# Sheet1.net
KiCad netlist of a schematic drawn in Altium Designer
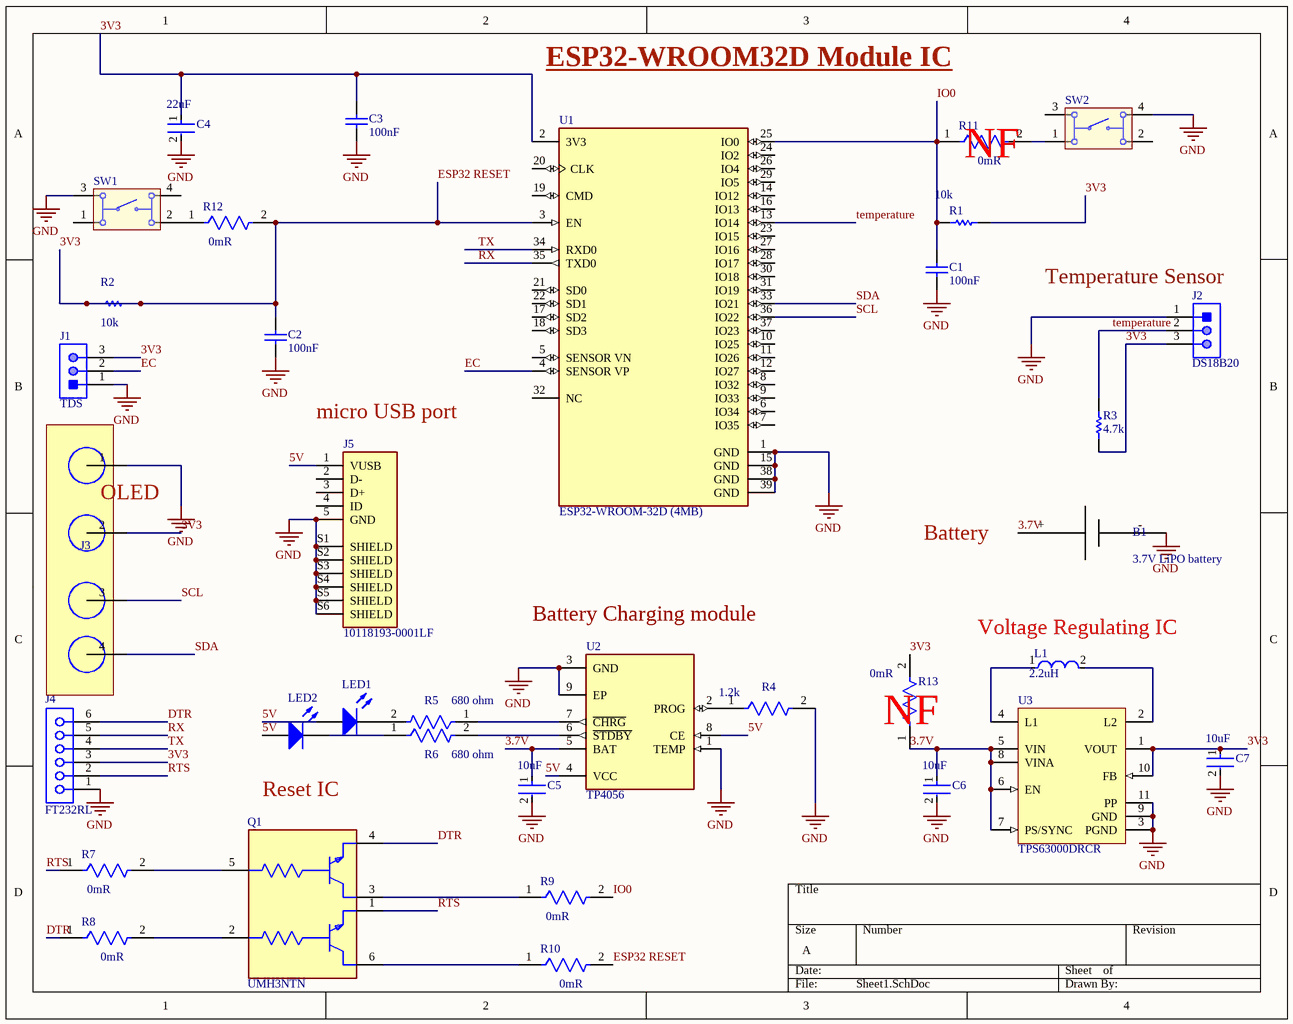
[diagram p0: Sheet1.SchDoc]

(export (version "E")
  (design (tool "Eeschema 10.0.6"))
  (components
    (comp (ref "B1")
      (value "3.7V LiPO battery")
      (footprint "Battery_lipo")
      (libsource (lib "*") (part "Battery"))
    )
    (comp (ref "C1")
      (value "MD015E104MAB")
      (footprint "AVX-MD01")
      (description "Ceramic Capacitor, 0.1 uF, +/- 20%, 50 V, -55 to 125 degC, 2-Pin THD (MD01), Bulk")
      (fields (field (name "MANUFACTURER") "AVX") (field (name "CAPACITANCE") "100nF"))
      (libsource (lib "Altium Content Vault") (part "CAP-NP-2"))
    )
    (comp (ref "C2")
      (value "MD015E104MAB")
      (footprint "AVX-MD01")
      (description "Ceramic Capacitor, 0.1 uF, +/- 20%, 50 V, -55 to 125 degC, 2-Pin THD (MD01), Bulk")
      (fields (field (name "MANUFACTURER") "AVX") (field (name "CAPACITANCE") "100nF"))
      (libsource (lib "Altium Content Vault") (part "CAP-NP-2"))
    )
    (comp (ref "C3")
      (value "MD015E104MAB")
      (footprint "AVX-MD01")
      (description "Ceramic Capacitor, 0.1 uF, +/- 20%, 50 V, -55 to 125 degC, 2-Pin THD (MD01), Bulk")
      (fields (field (name "MANUFACTURER") "AVX") (field (name "CAPACITANCE") "100nF"))
      (libsource (lib "Altium Content Vault") (part "CAP-NP-2"))
    )
    (comp (ref "C4")
      (value "RCER71E226MWM1H03A")
      (footprint "FP-RCEWM1-MFG")
      (description "CAP CER 22UF 25V X7R RADIAL")
      (fields (field (name "CAPACITANCE") "22uF") (field (name "TOLERANCE") "20%"))
      (libsource (lib "Altium Content Vault") (part "02cd4be3c70576c341d710602a673aa"))
    )
    (comp (ref "C5")
      (value "RCER71H106MWK1H03B")
      (footprint "FP-RCEWM1-MFG")
      (description "Cap Ceramic 10uF 50V X7R ±20% Radial 5mm +125°C Automotive Ammo Pack")
      (fields
        (field (name "CAPACITANCE") "10uF")
        (field (name "TOLERANCE") "20%")
        (field (name "VOLTAGE") "50V")
      )
      (libsource (lib "Altium Content Vault") (part "02cd4be3c70576c341d710602a673aa"))
    )
    (comp (ref "C6")
      (value "ECEA1VKN100")
      (footprint "FP-RAD-TH-D_6_3_0_5-L_7_1-MFG")
      (description "Aluminum Electrolytic Capacitors (Radial Lead Type) 10uF ±20% 35V")
      (fields (field (name "TOLERANCE") "20%") (field (name "CAPACITANCE") "10uF"))
      (libsource (lib "Altium Content Vault") (part "b4654b650e69147ec39a6b967a45e02"))
    )
    (comp (ref "C7")
      (value "ECEA1VKN100")
      (footprint "FP-RAD-TH-D_6_3_0_5-L_7_1-MFG")
      (description "Aluminum Electrolytic Capacitors (Radial Lead Type) 10uF ±20% 35V")
      (fields (field (name "TOLERANCE") "20%") (field (name "CAPACITANCE") "10uF"))
      (libsource (lib "Altium Content Vault") (part "b4654b650e69147ec39a6b967a45e02"))
    )
    (comp (ref "J1")
      (value "TDS")
      (footprint "MOLX-22-23-2031_V")
      (description "Male Header, Pitch 2.54 mm, 1 x 3 Position, Height 8.18 mm, Tail Length 3.56 mm, RoHS, Bulk")
      (fields (field (name "MANUFACTURER") "Molex"))
      (libsource (lib "Altium Content Vault") (part "CN-1P-M-R3"))
    )
    (comp (ref "J2")
      (value "DS18B20")
      (footprint "MOLX-22-23-2031_V")
      (description "Male Header, Pitch 2.54 mm, 1 x 3 Position, Height 8.18 mm, Tail Length 3.56 mm, RoHS, Bulk")
      (fields (field (name "MANUFACTURER") "Molex"))
      (libsource (lib "") (part "CN-1P-M-R3_1"))
    )
    (comp (ref "J3")
      (value "OLED")
      (footprint "female header")
      (libsource (lib "*") (part "4 PIN FEMALE HEADER"))
    )
    (comp (ref "J4")
      (value "FT232RL")
      (footprint "SMTC-SSW-106-02-X-S-RA")
      (fields (field (name "PARTNUMBER") "SSW-106-02-G-S-RA") (field (name "MANUFACTURER") "Samtec"))
      (libsource (lib "Altium Content Vault") (part "SMTC-SSW-106-02-X-S-X"))
    )
    (comp (ref "J5")
      (value "10118193-0001LF")
      (footprint "AMPHENOL_10118193-0001LF")
      (libsource (lib "Schlib1") (part "10118193-0001LF"))
    )
    (comp (ref "L1")
      (value "LQM2HPN2R2MJ0L")
      (footprint "FP-LQM2HPN_J0-IPC_A")
      (description "Multilayer Type Inductor for Power Lines, 1008 (2520), 2.2μH, 20%, 0.15Ω, 1000mA")
      (fields (field (name "TOLERANCE") "20%") (field (name "INDUCTANCE") "2.2uH"))
      (libsource (lib "Altium Content Vault") (part "725321dda6339637d4d059423bc1c3c"))
    )
    (comp (ref "LED1")
      (value "151051BS04000")
      (footprint "Type 5mm")
      (description "THT LED round mono-color color lens, WL-TMRW, Blue")
      (fields (field (name "MANUFACTURER") "Wuerth Elektronik"))
      (libsource (lib "Altium Content Vault") (part "WE-LED_K1A2-2"))
    )
    (comp (ref "LED2")
      (value "151051BS04000")
      (footprint "Type 5mm")
      (description "THT LED round mono-color color lens, WL-TMRW, Blue")
      (fields (field (name "MANUFACTURER") "Wuerth Elektronik"))
      (libsource (lib "Altium Content Vault") (part "WE-LED_K1A2-2"))
    )
    (comp (ref "Q1")
      (value "UMH3NTN")
      (footprint "FP-UMT6-IPC_C")
      (description "TRANS 2NPN PREBIAS 0.15W UMT6")
      (libsource (lib "Altium Content Vault") (part "8b681bbdef8deb96797ed10fcd55d9e"))
    )
    (comp (ref "R1")
      (value "OD103JE")
      (footprint "OMTE-RES7X2.5-2")
      (fields
        (field (name "RESISTANCE (OHMS)") "10k")
        (field (name "TOLERANCE") "±5%")
        (field (name "MANUFACTURER") "Ohmite")
      )
      (libsource (lib "Altium Content Vault") (part "RES-2"))
    )
    (comp (ref "R2")
      (value "OD103JE")
      (footprint "OMTE-RES7X2.5-2")
      (fields
        (field (name "RESISTANCE (OHMS)") "10k")
        (field (name "TOLERANCE") "±5%")
        (field (name "MANUFACTURER") "Ohmite")
      )
      (libsource (lib "Altium Content Vault") (part "RES-2"))
    )
    (comp (ref "R3")
      (value "OD103JE")
      (footprint "OMTE-RES7X2.5-2")
      (fields
        (field (name "RESISTANCE (OHMS)") "4.7k")
        (field (name "TOLERANCE") "±5%")
        (field (name "MANUFACTURER") "Ohmite")
      )
      (libsource (lib "Altium Content Vault") (part "RES-2"))
    )
    (comp (ref "R4")
      (value "MRS25000C9530FCT00")
      (footprint "FP-MRS25-MFG")
      (description "RES 953 OHM 0.6W 1% AXIAL")
      (fields (field (name "RESISTANCE") "1.2k") (field (name "TOLERANCE") "1%"))
      (libsource (lib "Altium Content Vault") (part "1029c3af85768c4190bb7ad29bc67b5"))
    )
    (comp (ref "R5")
      (value "MRS25000C9530FCT00")
      (footprint "FP-MRS25-MFG")
      (description "RES 953 OHM 0.6W 1% AXIAL")
      (fields (field (name "RESISTANCE") "680 ohm") (field (name "TOLERANCE") "1%"))
      (libsource (lib "Altium Content Vault") (part "1029c3af85768c4190bb7ad29bc67b5"))
    )
    (comp (ref "R6")
      (value "MRS25000C9530FCT00")
      (footprint "FP-MRS25-MFG")
      (description "RES 953 OHM 0.6W 1% AXIAL")
      (fields (field (name "RESISTANCE") "680 ohm") (field (name "TOLERANCE") "1%"))
      (libsource (lib "Altium Content Vault") (part "1029c3af85768c4190bb7ad29bc67b5"))
    )
    (comp (ref "R7")
      (value "ZOR-25-R-52-0R")
      (footprint "FP-ZOR-25-R-52-0R-MFG")
      (description "RES 0 OHM JUMPER 1/4W AXIAL")
      (fields (field (name "TOLERANCE") "5%") (field (name "RESISTANCE") "0mR"))
      (libsource (lib "Altium Content Vault") (part "d029466b076adaef5daba0b7f088f1c"))
    )
    (comp (ref "R8")
      (value "ZOR-25-R-52-0R")
      (footprint "FP-ZOR-25-R-52-0R-MFG")
      (description "RES 0 OHM JUMPER 1/4W AXIAL")
      (fields (field (name "TOLERANCE") "5%") (field (name "RESISTANCE") "0mR"))
      (libsource (lib "Altium Content Vault") (part "d029466b076adaef5daba0b7f088f1c"))
    )
    (comp (ref "R9")
      (value "ZOR-25-R-52-0R")
      (footprint "FP-ZOR-25-R-52-0R-MFG")
      (description "RES 0 OHM JUMPER 1/4W AXIAL")
      (fields (field (name "TOLERANCE") "5%") (field (name "RESISTANCE") "0mR"))
      (libsource (lib "Altium Content Vault") (part "d029466b076adaef5daba0b7f088f1c"))
    )
    (comp (ref "R10")
      (value "ZOR-25-R-52-0R")
      (footprint "FP-ZOR-25-R-52-0R-MFG")
      (description "RES 0 OHM JUMPER 1/4W AXIAL")
      (fields (field (name "TOLERANCE") "5%") (field (name "RESISTANCE") "0mR"))
      (libsource (lib "Altium Content Vault") (part "d029466b076adaef5daba0b7f088f1c"))
    )
    (comp (ref "R11")
      (value "ZOR-25-R-52-0R")
      (footprint "FP-ZOR-25-R-52-0R-MFG")
      (description "RES 0 OHM JUMPER 1/4W AXIAL")
      (fields (field (name "TOLERANCE") "5%") (field (name "RESISTANCE") "0mR"))
      (libsource (lib "Altium Content Vault") (part "d029466b076adaef5daba0b7f088f1c"))
    )
    (comp (ref "R12")
      (value "ZOR-25-R-52-0R")
      (footprint "FP-ZOR-25-R-52-0R-MFG")
      (description "RES 0 OHM JUMPER 1/4W AXIAL")
      (fields (field (name "TOLERANCE") "5%") (field (name "RESISTANCE") "0mR"))
      (libsource (lib "Altium Content Vault") (part "d029466b076adaef5daba0b7f088f1c"))
    )
    (comp (ref "R13")
      (value "ZOR-25-R-52-0R")
      (footprint "FP-ZOR-25-R-52-0R-MFG")
      (description "RES 0 OHM JUMPER 1/4W AXIAL")
      (fields (field (name "TOLERANCE") "5%") (field (name "RESISTANCE") "0mR"))
      (libsource (lib "Altium Content Vault") (part "d029466b076adaef5daba0b7f088f1c"))
    )
    (comp (ref "SW1")
      (value "430156050726")
      (footprint "430156050726")
      (description "WS-TATV THT Tact Switch 6X6 mm")
      (fields (field (name "MANUFACTURER") "Wuerth Elektronik"))
      (libsource (lib "Altium Content Vault") (part "WE-TACT-SW-4"))
    )
    (comp (ref "SW2")
      (value "430156050726")
      (footprint "430156050726")
      (description "WS-TATV THT Tact Switch 6X6 mm")
      (fields (field (name "MANUFACTURER") "Wuerth Elektronik"))
      (libsource (lib "Altium Content Vault") (part "WE-TACT-SW-4"))
    )
    (comp (ref "U1")
      (value "ESP32-WROOM-32D (4MB)")
      (footprint "FP-ESP32-WROOM-32D_4MB-MFG")
      (description "RX TXRX MOD WIFI TRACE ANT SMD")
      (libsource (lib "Altium Content Vault") (part "ee866abf0b6c51247b7f5cdebf2f250"))
    )
    (comp (ref "U2")
      (value "TP4056")
      (footprint "SOP127P600X175-9N")
      (libsource (lib "Schlib1") (part "TP4056"))
    )
    (comp (ref "U3")
      (value "TPS63000DRCR")
      (footprint "DRC0010J_V")
      (fields (field (name "MANUFACTURER") "Texas Instruments"))
      (libsource (lib "Altium Content Vault") (part "TI-TPS63000DRC10-3000X1650TP"))
    )
  )
  (nets
    (net (code "1") (name "/3.7V") (class "Default")
      (node (ref "B1") (pin "+") (pinfunction "SDA_+") (pintype "passive"))
      (node (ref "C5") (pin "1") (pinfunction "1_1") (pintype "passive"))
      (node (ref "C6") (pin "1") (pinfunction "1_1") (pintype "passive"))
      (node (ref "R13") (pin "1") (pinfunction "1_1") (pintype "passive"))
      (node (ref "U2") (pin "5") (pinfunction "BAT_5") (pintype "passive"))
      (node (ref "U3") (pin "5") (pinfunction "VIN_5") (pintype "power_in"))
      (node (ref "U3") (pin "6") (pinfunction "EN_6") (pintype "input"))
      (node (ref "U3") (pin "7") (pinfunction "PS/SYNC_7") (pintype "input"))
      (node (ref "U3") (pin "8") (pinfunction "VINA_8") (pintype "power_in"))
    )
    (net (code "2") (name "/3V3") (class "Default")
      (node (ref "C2") (pin "2") (pinfunction "2_2") (pintype "passive"))
      (node (ref "C3") (pin "2") (pinfunction "2_2") (pintype "passive"))
      (node (ref "C4") (pin "1") (pinfunction "1_1") (pintype "passive"))
      (node (ref "C7") (pin "1") (pinfunction "1_1") (pintype "passive"))
      (node (ref "J1") (pin "3") (pinfunction "3_3") (pintype "passive"))
      (node (ref "J2") (pin "3") (pinfunction "3_3") (pintype "passive"))
      (node (ref "J3") (pin "2") (pinfunction "2_2") (pintype "passive"))
      (node (ref "J4") (pin "3") (pinfunction "3_3") (pintype "passive"))
      (node (ref "R1") (pin "2") (pinfunction "2_2") (pintype "passive"))
      (node (ref "R10") (pin "2") (pinfunction "2_2") (pintype "passive"))
      (node (ref "R12") (pin "2") (pinfunction "2_2") (pintype "passive"))
      (node (ref "R13") (pin "2") (pinfunction "2_2") (pintype "passive"))
      (node (ref "R2") (pin "1") (pinfunction "1_1") (pintype "passive"))
      (node (ref "R2") (pin "2") (pinfunction "2_2") (pintype "passive"))
      (node (ref "R3") (pin "1") (pinfunction "1_1") (pintype "passive"))
      (node (ref "U1") (pin "2") (pinfunction "3V3_2") (pintype "power_in"))
      (node (ref "U1") (pin "3") (pinfunction "EN_3") (pintype "input"))
      (node (ref "U3") (pin "1") (pinfunction "VOUT_1") (pintype "power_in"))
      (node (ref "U3") (pin "10") (pinfunction "FB_10") (pintype "input"))
    )
    (net (code "3") (name "/5V") (class "Default")
      (node (ref "J5") (pin "1") (pinfunction "VUSB_1") (pintype "passive"))
      (node (ref "LED1") (pin "2") (pinfunction "A_2") (pintype "passive"))
      (node (ref "LED2") (pin "2") (pinfunction "A_2") (pintype "passive"))
      (node (ref "U2") (pin "4") (pinfunction "VCC_4") (pintype "power_in"))
      (node (ref "U2") (pin "8") (pinfunction "CE_8") (pintype "input"))
    )
    (net (code "4") (name "/DTR") (class "Default")
      (node (ref "J4") (pin "6") (pinfunction "6_6") (pintype "passive"))
      (node (ref "Q1") (pin "4") (pinfunction "E_4") (pintype "passive"))
      (node (ref "R8") (pin "1") (pinfunction "1_1") (pintype "passive"))
    )
    (net (code "5") (name "/EC") (class "Default")
      (node (ref "J1") (pin "2") (pinfunction "2_2") (pintype "passive"))
      (node (ref "U1") (pin "4") (pinfunction "SENSOR_VP_4") (pintype "bidirectional"))
    )
    (net (code "6") (name "/IO0") (class "Default")
      (node (ref "C1") (pin "2") (pinfunction "2_2") (pintype "passive"))
      (node (ref "R1") (pin "1") (pinfunction "1_1") (pintype "passive"))
      (node (ref "R11") (pin "1") (pinfunction "1_1") (pintype "passive"))
      (node (ref "R9") (pin "2") (pinfunction "2_2") (pintype "passive"))
      (node (ref "U1") (pin "25") (pinfunction "IO0_25") (pintype "bidirectional"))
    )
    (net (code "7") (name "/RTS") (class "Default")
      (node (ref "J4") (pin "2") (pinfunction "2_2") (pintype "passive"))
      (node (ref "Q1") (pin "1") (pinfunction "E_1") (pintype "passive"))
      (node (ref "R7") (pin "1") (pinfunction "1_1") (pintype "passive"))
    )
    (net (code "8") (name "/RX") (class "Default")
      (node (ref "J4") (pin "5") (pinfunction "5_5") (pintype "passive"))
      (node (ref "U1") (pin "35") (pinfunction "TXD0_35") (pintype "output"))
    )
    (net (code "9") (name "/SCL") (class "Default")
      (node (ref "J3") (pin "3") (pinfunction "3_3") (pintype "passive"))
      (node (ref "U1") (pin "36") (pinfunction "IO22_36") (pintype "bidirectional"))
    )
    (net (code "10") (name "/SDA") (class "Default")
      (node (ref "J3") (pin "4") (pinfunction "4_4") (pintype "passive"))
      (node (ref "U1") (pin "33") (pinfunction "IO21_33") (pintype "bidirectional"))
    )
    (net (code "11") (name "/TX") (class "Default")
      (node (ref "J4") (pin "4") (pinfunction "4_4") (pintype "passive"))
      (node (ref "U1") (pin "34") (pinfunction "RXD0_34") (pintype "input"))
    )
    (net (code "12") (name "/temperature") (class "Default")
      (node (ref "J2") (pin "2") (pinfunction "2_2") (pintype "passive"))
      (node (ref "R3") (pin "2") (pinfunction "2_2") (pintype "passive"))
      (node (ref "U1") (pin "13") (pinfunction "IO14_13") (pintype "bidirectional"))
    )
    (net (code "13") (name "GND") (class "Default")
      (node (ref "B1") (pin "-") (pinfunction "SDA_-") (pintype "passive"))
      (node (ref "C1") (pin "1") (pinfunction "1_1") (pintype "passive"))
      (node (ref "C2") (pin "1") (pinfunction "1_1") (pintype "passive"))
      (node (ref "C3") (pin "1") (pinfunction "1_1") (pintype "passive"))
      (node (ref "C4") (pin "2") (pinfunction "2_2") (pintype "passive"))
      (node (ref "C5") (pin "2") (pinfunction "2_2") (pintype "passive"))
      (node (ref "C6") (pin "2") (pinfunction "2_2") (pintype "passive"))
      (node (ref "C7") (pin "2") (pinfunction "2_2") (pintype "passive"))
      (node (ref "J1") (pin "1") (pinfunction "1_1") (pintype "passive"))
      (node (ref "J2") (pin "1") (pinfunction "1_1") (pintype "passive"))
      (node (ref "J3") (pin "1") (pinfunction "1_1") (pintype "passive"))
      (node (ref "J4") (pin "1") (pinfunction "1_1") (pintype "passive"))
      (node (ref "J5") (pin "5") (pinfunction "GND_5") (pintype "passive"))
      (node (ref "J5") (pin "S1") (pinfunction "SHIELD_S1") (pintype "passive"))
      (node (ref "J5") (pin "S2") (pinfunction "SHIELD_S2") (pintype "passive"))
      (node (ref "J5") (pin "S3") (pinfunction "SHIELD_S3") (pintype "passive"))
      (node (ref "J5") (pin "S4") (pinfunction "SHIELD_S4") (pintype "passive"))
      (node (ref "J5") (pin "S5") (pinfunction "SHIELD_S5") (pintype "passive"))
      (node (ref "J5") (pin "S6") (pinfunction "SHIELD_S6") (pintype "passive"))
      (node (ref "R4") (pin "2") (pinfunction "2_2") (pintype "passive"))
      (node (ref "SW1") (pin "3") (pinfunction "3_3") (pintype "passive"))
      (node (ref "SW2") (pin "4") (pinfunction "4_4") (pintype "passive"))
      (node (ref "U1") (pin "1") (pinfunction "GND_1") (pintype "power_in"))
      (node (ref "U1") (pin "15") (pinfunction "GND_15") (pintype "power_in"))
      (node (ref "U1") (pin "38") (pinfunction "GND_38") (pintype "power_in"))
      (node (ref "U1") (pin "39") (pinfunction "GND_39") (pintype "power_in"))
      (node (ref "U2") (pin "1") (pinfunction "TEMP_1") (pintype "input"))
      (node (ref "U2") (pin "3") (pinfunction "GND_3") (pintype "power_in"))
      (node (ref "U2") (pin "9") (pinfunction "EP_9") (pintype "passive"))
      (node (ref "U3") (pin "11") (pinfunction "PP_11") (pintype "power_in"))
      (node (ref "U3") (pin "3") (pinfunction "PGND_3") (pintype "power_in"))
      (node (ref "U3") (pin "9") (pinfunction "GND_9") (pintype "power_in"))
    )
    (net (code "14") (name "Net-(LED1-K)") (class "Default")
      (node (ref "LED1") (pin "1") (pinfunction "K_1") (pintype "passive"))
      (node (ref "R5") (pin "2") (pinfunction "2_2") (pintype "passive"))
    )
    (net (code "15") (name "Net-(LED2-K)") (class "Default")
      (node (ref "LED2") (pin "1") (pinfunction "K_1") (pintype "passive"))
      (node (ref "R6") (pin "1") (pinfunction "1_1") (pintype "passive"))
    )
    (net (code "16") (name "Net-(Q1-B-Pad2)") (class "Default")
      (node (ref "Q1") (pin "2") (pinfunction "B_2") (pintype "passive"))
      (node (ref "R8") (pin "2") (pinfunction "2_2") (pintype "passive"))
    )
    (net (code "17") (name "Net-(Q1-B-Pad5)") (class "Default")
      (node (ref "Q1") (pin "5") (pinfunction "B_5") (pintype "passive"))
      (node (ref "R7") (pin "2") (pinfunction "2_2") (pintype "passive"))
    )
    (net (code "18") (name "Net-(Q1-C-Pad3)") (class "Default")
      (node (ref "Q1") (pin "3") (pinfunction "C_3") (pintype "passive"))
      (node (ref "R9") (pin "1") (pinfunction "1_1") (pintype "passive"))
    )
    (net (code "19") (name "Net-(Q1-C-Pad6)") (class "Default")
      (node (ref "Q1") (pin "6") (pinfunction "C_6") (pintype "passive"))
      (node (ref "R10") (pin "1") (pinfunction "1_1") (pintype "passive"))
    )
    (net (code "20") (name "Net-(R11-Pad2)") (class "Default")
      (node (ref "R11") (pin "2") (pinfunction "2_2") (pintype "passive"))
      (node (ref "SW2") (pin "1") (pinfunction "1_1") (pintype "passive"))
    )
    (net (code "21") (name "Net-(R12-Pad1)") (class "Default")
      (node (ref "R12") (pin "1") (pinfunction "1_1") (pintype "passive"))
      (node (ref "SW1") (pin "2") (pinfunction "2_2") (pintype "passive"))
    )
    (net (code "22") (name "Net-(U2-PROG)") (class "Default")
      (node (ref "R4") (pin "1") (pinfunction "1_1") (pintype "passive"))
      (node (ref "U2") (pin "2") (pinfunction "PROG_2") (pintype "bidirectional"))
    )
    (net (code "23") (name "Net-(U2-~{CHRG})") (class "Default")
      (node (ref "R5") (pin "1") (pinfunction "1_1") (pintype "passive"))
      (node (ref "U2") (pin "7") (pinfunction "~{CHRG}_7") (pintype "output"))
    )
    (net (code "24") (name "Net-(U2-~{STDBY})") (class "Default")
      (node (ref "R6") (pin "2") (pinfunction "2_2") (pintype "passive"))
      (node (ref "U2") (pin "6") (pinfunction "~{STDBY}_6") (pintype "output"))
    )
    (net (code "25") (name "Net-(U3-L1)") (class "Default")
      (node (ref "L1") (pin "1") (pinfunction "1_1") (pintype "passive"))
      (node (ref "U3") (pin "4") (pinfunction "L1_4") (pintype "passive"))
    )
    (net (code "26") (name "Net-(U3-L2)") (class "Default")
      (node (ref "L1") (pin "2") (pinfunction "2_2") (pintype "passive"))
      (node (ref "U3") (pin "2") (pinfunction "L2_2") (pintype "passive"))
    )
    (net (code "27") (name "unconnected-(J5-D+-Pad3)") (class "Default")
      (node (ref "J5") (pin "3") (pinfunction "D+_3") (pintype "passive"))
    )
    (net (code "28") (name "unconnected-(J5-D--Pad2)") (class "Default")
      (node (ref "J5") (pin "2") (pinfunction "D-_2") (pintype "passive"))
    )
    (net (code "29") (name "unconnected-(J5-ID-Pad4)") (class "Default")
      (node (ref "J5") (pin "4") (pinfunction "ID_4") (pintype "passive"))
    )
    (net (code "30") (name "unconnected-(SW1-Pad1)") (class "Default")
      (node (ref "SW1") (pin "1") (pinfunction "1_1") (pintype "passive"))
    )
    (net (code "31") (name "unconnected-(SW1-Pad4)") (class "Default")
      (node (ref "SW1") (pin "4") (pinfunction "4_4") (pintype "passive"))
    )
    (net (code "32") (name "unconnected-(SW2-Pad2)") (class "Default")
      (node (ref "SW2") (pin "2") (pinfunction "2_2") (pintype "passive"))
    )
    (net (code "33") (name "unconnected-(SW2-Pad3)") (class "Default")
      (node (ref "SW2") (pin "3") (pinfunction "3_3") (pintype "passive"))
    )
    (net (code "34") (name "unconnected-(U1-CLK-Pad20)") (class "Default")
      (node (ref "U1") (pin "20") (pinfunction "CLK_20") (pintype "bidirectional"))
    )
    (net (code "35") (name "unconnected-(U1-CMD-Pad19)") (class "Default")
      (node (ref "U1") (pin "19") (pinfunction "CMD_19") (pintype "bidirectional"))
    )
    (net (code "36") (name "unconnected-(U1-IO2-Pad24)") (class "Default")
      (node (ref "U1") (pin "24") (pinfunction "IO2_24") (pintype "bidirectional"))
    )
    (net (code "37") (name "unconnected-(U1-IO4-Pad26)") (class "Default")
      (node (ref "U1") (pin "26") (pinfunction "IO4_26") (pintype "bidirectional"))
    )
    (net (code "38") (name "unconnected-(U1-IO5-Pad29)") (class "Default")
      (node (ref "U1") (pin "29") (pinfunction "IO5_29") (pintype "bidirectional"))
    )
    (net (code "39") (name "unconnected-(U1-IO12-Pad14)") (class "Default")
      (node (ref "U1") (pin "14") (pinfunction "IO12_14") (pintype "bidirectional"))
    )
    (net (code "40") (name "unconnected-(U1-IO13-Pad16)") (class "Default")
      (node (ref "U1") (pin "16") (pinfunction "IO13_16") (pintype "bidirectional"))
    )
    (net (code "41") (name "unconnected-(U1-IO15-Pad23)") (class "Default")
      (node (ref "U1") (pin "23") (pinfunction "IO15_23") (pintype "bidirectional"))
    )
    (net (code "42") (name "unconnected-(U1-IO16-Pad27)") (class "Default")
      (node (ref "U1") (pin "27") (pinfunction "IO16_27") (pintype "bidirectional"))
    )
    (net (code "43") (name "unconnected-(U1-IO17-Pad28)") (class "Default")
      (node (ref "U1") (pin "28") (pinfunction "IO17_28") (pintype "bidirectional"))
    )
    (net (code "44") (name "unconnected-(U1-IO18-Pad30)") (class "Default")
      (node (ref "U1") (pin "30") (pinfunction "IO18_30") (pintype "bidirectional"))
    )
    (net (code "45") (name "unconnected-(U1-IO19-Pad31)") (class "Default")
      (node (ref "U1") (pin "31") (pinfunction "IO19_31") (pintype "bidirectional"))
    )
    (net (code "46") (name "unconnected-(U1-IO23-Pad37)") (class "Default")
      (node (ref "U1") (pin "37") (pinfunction "IO23_37") (pintype "bidirectional"))
    )
    (net (code "47") (name "unconnected-(U1-IO25-Pad10)") (class "Default")
      (node (ref "U1") (pin "10") (pinfunction "IO25_10") (pintype "bidirectional"))
    )
    (net (code "48") (name "unconnected-(U1-IO26-Pad11)") (class "Default")
      (node (ref "U1") (pin "11") (pinfunction "IO26_11") (pintype "bidirectional"))
    )
    (net (code "49") (name "unconnected-(U1-IO27-Pad12)") (class "Default")
      (node (ref "U1") (pin "12") (pinfunction "IO27_12") (pintype "bidirectional"))
    )
    (net (code "50") (name "unconnected-(U1-IO32-Pad8)") (class "Default")
      (node (ref "U1") (pin "8") (pinfunction "IO32_8") (pintype "bidirectional"))
    )
    (net (code "51") (name "unconnected-(U1-IO33-Pad9)") (class "Default")
      (node (ref "U1") (pin "9") (pinfunction "IO33_9") (pintype "bidirectional"))
    )
    (net (code "52") (name "unconnected-(U1-IO34-Pad6)") (class "Default")
      (node (ref "U1") (pin "6") (pinfunction "IO34_6") (pintype "bidirectional"))
    )
    (net (code "53") (name "unconnected-(U1-IO35-Pad7)") (class "Default")
      (node (ref "U1") (pin "7") (pinfunction "IO35_7") (pintype "bidirectional"))
    )
    (net (code "54") (name "unconnected-(U1-NC-Pad32)") (class "Default")
      (node (ref "U1") (pin "32") (pinfunction "NC_32") (pintype "passive"))
    )
    (net (code "55") (name "unconnected-(U1-SD0-Pad21)") (class "Default")
      (node (ref "U1") (pin "21") (pinfunction "SD0_21") (pintype "bidirectional"))
    )
    (net (code "56") (name "unconnected-(U1-SD1-Pad22)") (class "Default")
      (node (ref "U1") (pin "22") (pinfunction "SD1_22") (pintype "bidirectional"))
    )
    (net (code "57") (name "unconnected-(U1-SD2-Pad17)") (class "Default")
      (node (ref "U1") (pin "17") (pinfunction "SD2_17") (pintype "bidirectional"))
    )
    (net (code "58") (name "unconnected-(U1-SD3-Pad18)") (class "Default")
      (node (ref "U1") (pin "18") (pinfunction "SD3_18") (pintype "bidirectional"))
    )
    (net (code "59") (name "unconnected-(U1-SENSOR_VN-Pad5)") (class "Default")
      (node (ref "U1") (pin "5") (pinfunction "SENSOR_VN_5") (pintype "bidirectional"))
    )
  )
)
